# CellVoltageControl.net
KiCad netlist of a schematic drawn in Altium Designer
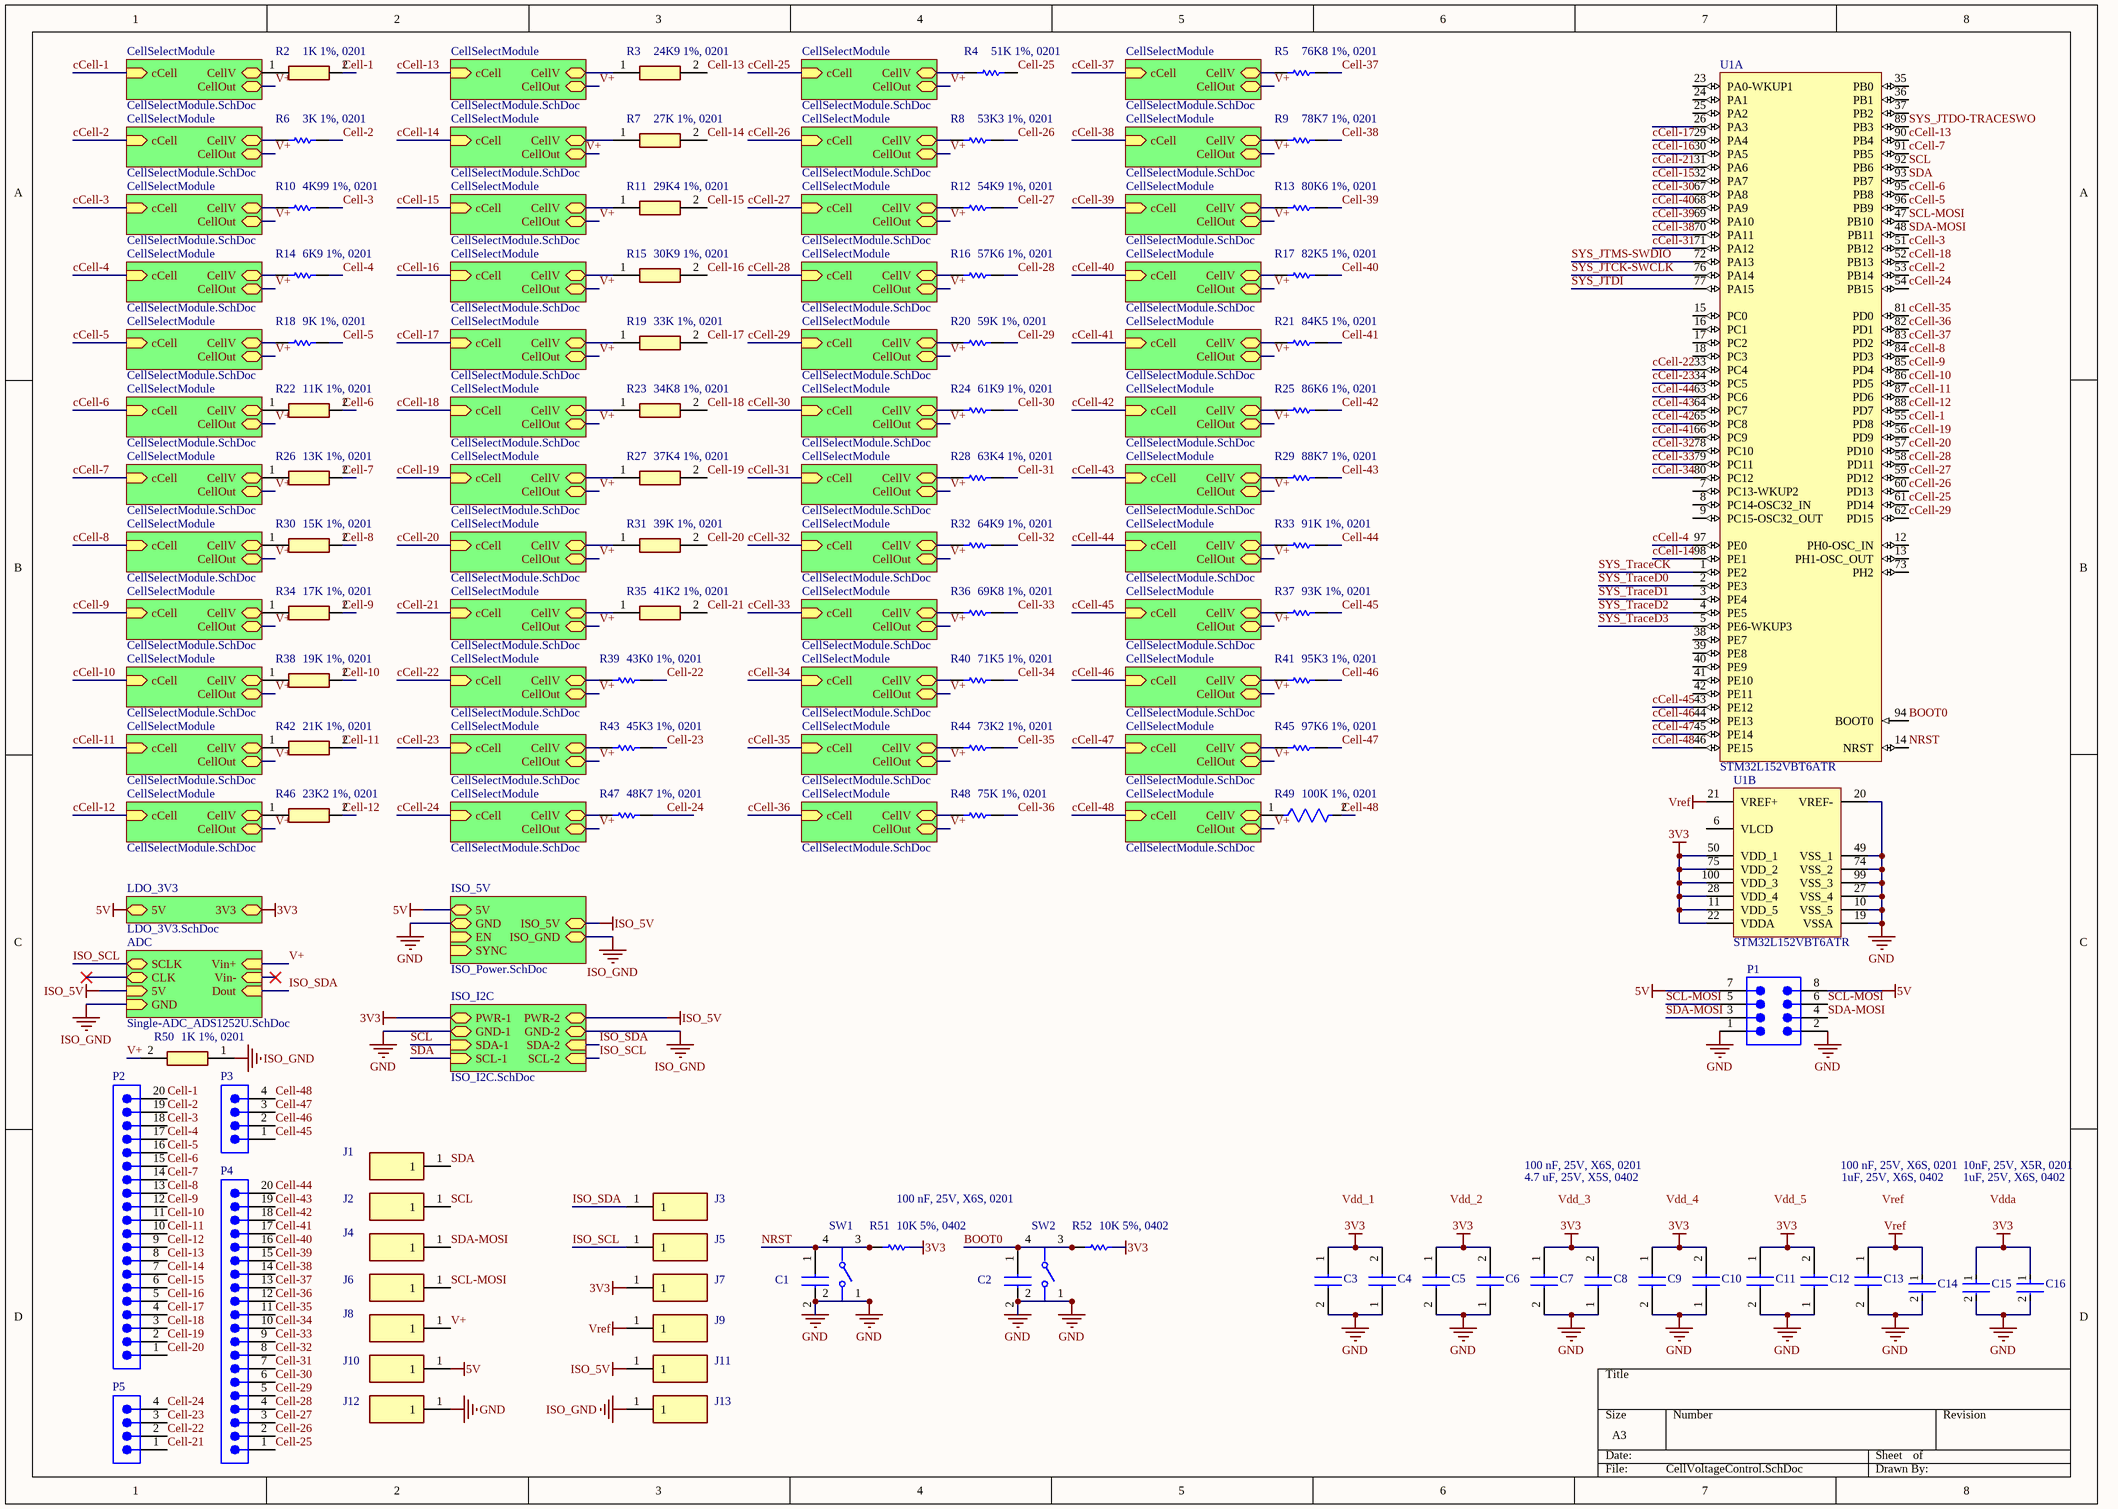
[diagram p0: CellVoltageControl.SchDoc]

(export (version "E")
  (design (tool "Eeschema 10.0.6"))
  (components
    (comp (ref "C1")
      (value "100 nF, 25V, X6S, 0201")
      (footprint "SamacSys:CAPC0603X33N")
      (description "Capacitor")
      (fields
        (field (name "MANUFACTURER_PART_NUMBER") "GRM033C81E104KE14D")
        (field (name "MOUSER PART NUMBER") "81-GRM33C81E104KE14D")
      )
      (libsource (lib "*") (part "GRM033C81E104KE14D"))
    )
    (comp (ref "C2")
      (value "100 nF, 25V, X6S, 0201")
      (footprint "SamacSys:CAPC0603X33N")
      (description "Capacitor")
      (fields
        (field (name "MANUFACTURER_PART_NUMBER") "GRM033C81E104KE14D")
        (field (name "MOUSER PART NUMBER") "81-GRM33C81E104KE14D")
      )
      (libsource (lib "*") (part "GRM033C81E104KE14D"))
    )
    (comp (ref "C3")
      (value "100 nF, 25V, X6S, 0201")
      (footprint "SamacSys:CAPC0603X33N")
      (description "Capacitor")
      (fields
        (field (name "MANUFACTURER_PART_NUMBER") "GRM033C81E104KE14D")
        (field (name "MOUSER PART NUMBER") "81-GRM33C81E104KE14D")
      )
      (libsource (lib "*") (part "GRM033C81E104KE14D"))
    )
    (comp (ref "C4")
      (value "4.7 uF, 25V, X5S, 0402")
      (footprint "SamacSys:GRM15x")
      (description "Capacitor")
      (fields
        (field (name "MANUFACTURER_PART_NUMBER") "GRM155C61E475ME15J")
        (field (name "MOUSER PART NUMBER") "81-GRM15C61E475ME15J")
      )
      (libsource (lib "*") (part "GRM155C61E475ME15J"))
    )
    (comp (ref "C5")
      (value "100 nF, 25V, X6S, 0201")
      (footprint "SamacSys:CAPC0603X33N")
      (description "Capacitor")
      (fields
        (field (name "MANUFACTURER_PART_NUMBER") "GRM033C81E104KE14D")
        (field (name "MOUSER PART NUMBER") "81-GRM33C81E104KE14D")
      )
      (libsource (lib "*") (part "GRM033C81E104KE14D"))
    )
    (comp (ref "C6")
      (value "4.7 uF, 25V, X5S, 0402")
      (footprint "SamacSys:GRM15x")
      (description "Capacitor")
      (fields
        (field (name "MANUFACTURER_PART_NUMBER") "GRM155C61E475ME15J")
        (field (name "MOUSER PART NUMBER") "81-GRM15C61E475ME15J")
      )
      (libsource (lib "*") (part "GRM155C61E475ME15J"))
    )
    (comp (ref "C7")
      (value "100 nF, 25V, X6S, 0201")
      (footprint "SamacSys:CAPC0603X33N")
      (description "Capacitor")
      (fields
        (field (name "MANUFACTURER_PART_NUMBER") "GRM033C81E104KE14D")
        (field (name "MOUSER PART NUMBER") "81-GRM33C81E104KE14D")
      )
      (libsource (lib "*") (part "GRM033C81E104KE14D"))
    )
    (comp (ref "C8")
      (value "4.7 uF, 25V, X5S, 0402")
      (footprint "SamacSys:GRM15x")
      (description "Capacitor")
      (fields
        (field (name "MANUFACTURER_PART_NUMBER") "GRM155C61E475ME15J")
        (field (name "MOUSER PART NUMBER") "81-GRM15C61E475ME15J")
      )
      (libsource (lib "*") (part "GRM155C61E475ME15J"))
    )
    (comp (ref "C9")
      (value "100 nF, 25V, X6S, 0201")
      (footprint "SamacSys:CAPC0603X33N")
      (description "Capacitor")
      (fields
        (field (name "MANUFACTURER_PART_NUMBER") "GRM033C81E104KE14D")
        (field (name "MOUSER PART NUMBER") "81-GRM33C81E104KE14D")
      )
      (libsource (lib "*") (part "GRM033C81E104KE14D"))
    )
    (comp (ref "C10")
      (value "4.7 uF, 25V, X5S, 0402")
      (footprint "SamacSys:GRM15x")
      (description "Capacitor")
      (fields
        (field (name "MANUFACTURER_PART_NUMBER") "GRM155C61E475ME15J")
        (field (name "MOUSER PART NUMBER") "81-GRM15C61E475ME15J")
      )
      (libsource (lib "*") (part "GRM155C61E475ME15J"))
    )
    (comp (ref "C11")
      (value "100 nF, 25V, X6S, 0201")
      (footprint "SamacSys:CAPC0603X33N")
      (description "Capacitor")
      (fields
        (field (name "MANUFACTURER_PART_NUMBER") "GRM033C81E104KE14D")
        (field (name "MOUSER PART NUMBER") "81-GRM33C81E104KE14D")
      )
      (libsource (lib "*") (part "GRM033C81E104KE14D"))
    )
    (comp (ref "C12")
      (value "4.7 uF, 25V, X5S, 0402")
      (footprint "SamacSys:GRM15x")
      (description "Capacitor")
      (fields
        (field (name "MANUFACTURER_PART_NUMBER") "GRM155C61E475ME15J")
        (field (name "MOUSER PART NUMBER") "81-GRM15C61E475ME15J")
      )
      (libsource (lib "*") (part "GRM155C61E475ME15J"))
    )
    (comp (ref "C13")
      (value "100 nF, 25V, X6S, 0201")
      (footprint "SamacSys:CAPC0603X33N")
      (description "Capacitor")
      (fields
        (field (name "MANUFACTURER_PART_NUMBER") "GRM033C81E104KE14D")
        (field (name "MOUSER PART NUMBER") "81-GRM33C81E104KE14D")
      )
      (libsource (lib "*") (part "GRM033C81E104KE14D"))
    )
    (comp (ref "C14")
      (value "1uF, 25V, X6S, 0402")
      (footprint "FP-GRT155-0_1-IPC_A")
      (description "Multi-Layer Ceramic Capacitor 1uF 25V X6S ±10% 0402 Paper T/R")
      (libsource (lib "Altium Content Vault") (part "02cd4be3c70576c341d710602a673aa"))
    )
    (comp (ref "C15")
      (value "10nF, 25V, X5R, 0201")
      (footprint "FP-GRM033-0_03-IPC_C")
      (description "Chip Multilayer Ceramic Capacitors for General Purpose, 0201, 10000pF, X5R, 15%, 10%, 25V")
      (fields (field (name "TOLERANCE") "10%") (field (name "VOLTAGE") "25V"))
      (libsource (lib "Altium Content Vault") (part "b4654b650e69147ec39a6b967a45e02"))
    )
    (comp (ref "C16")
      (value "1uF, 25V, X6S, 0402")
      (footprint "FP-GRT155-0_1-IPC_A")
      (description "Multi-Layer Ceramic Capacitor 1uF 25V X6S ±10% 0402 Paper T/R")
      (libsource (lib "Altium Content Vault") (part "02cd4be3c70576c341d710602a673aa"))
    )
    (comp (ref "J1")
      (value "TestPad")
      (footprint "SamacSys:TestPad")
      (description "Connector")
      (fields
        (field (name "MANUFACTURER_PART_NUMBER") "61300111121")
        (field (name "MOUSER PART NUMBER") "710-61300111121")
      )
      (libsource (lib "*") (part "61300111121"))
    )
    (comp (ref "J2")
      (value "TestPad")
      (footprint "SamacSys:TestPad")
      (description "Connector")
      (fields
        (field (name "MANUFACTURER_PART_NUMBER") "61300111121")
        (field (name "MOUSER PART NUMBER") "710-61300111121")
      )
      (libsource (lib "*") (part "61300111121"))
    )
    (comp (ref "J3")
      (value "TestPad")
      (footprint "SamacSys:TestPad")
      (description "Connector")
      (fields
        (field (name "MANUFACTURER_PART_NUMBER") "61300111121")
        (field (name "MOUSER PART NUMBER") "710-61300111121")
      )
      (libsource (lib "") (part "61300111121_1"))
    )
    (comp (ref "J4")
      (value "TestPad")
      (footprint "SamacSys:TestPad")
      (description "Connector")
      (fields
        (field (name "MANUFACTURER_PART_NUMBER") "61300111121")
        (field (name "MOUSER PART NUMBER") "710-61300111121")
      )
      (libsource (lib "*") (part "61300111121"))
    )
    (comp (ref "J5")
      (value "TestPad")
      (footprint "SamacSys:TestPad")
      (description "Connector")
      (fields
        (field (name "MANUFACTURER_PART_NUMBER") "61300111121")
        (field (name "MOUSER PART NUMBER") "710-61300111121")
      )
      (libsource (lib "") (part "61300111121_1"))
    )
    (comp (ref "J6")
      (value "TestPad")
      (footprint "SamacSys:TestPad")
      (description "Connector")
      (fields
        (field (name "MANUFACTURER_PART_NUMBER") "61300111121")
        (field (name "MOUSER PART NUMBER") "710-61300111121")
      )
      (libsource (lib "*") (part "61300111121"))
    )
    (comp (ref "J7")
      (value "TestPad")
      (footprint "SamacSys:TestPad")
      (description "Connector")
      (fields
        (field (name "MANUFACTURER_PART_NUMBER") "61300111121")
        (field (name "MOUSER PART NUMBER") "710-61300111121")
      )
      (libsource (lib "") (part "61300111121_1"))
    )
    (comp (ref "J8")
      (value "TestPad")
      (footprint "SamacSys:TestPad")
      (description "Connector")
      (fields
        (field (name "MANUFACTURER_PART_NUMBER") "61300111121")
        (field (name "MOUSER PART NUMBER") "710-61300111121")
      )
      (libsource (lib "*") (part "61300111121"))
    )
    (comp (ref "J9")
      (value "TestPad")
      (footprint "SamacSys:TestPad")
      (description "Connector")
      (fields
        (field (name "MANUFACTURER_PART_NUMBER") "61300111121")
        (field (name "MOUSER PART NUMBER") "710-61300111121")
      )
      (libsource (lib "") (part "61300111121_1"))
    )
    (comp (ref "J10")
      (value "TestPad")
      (footprint "SamacSys:TestPad")
      (description "Connector")
      (fields
        (field (name "MANUFACTURER_PART_NUMBER") "61300111121")
        (field (name "MOUSER PART NUMBER") "710-61300111121")
      )
      (libsource (lib "*") (part "61300111121"))
    )
    (comp (ref "J11")
      (value "TestPad")
      (footprint "SamacSys:TestPad")
      (description "Connector")
      (fields
        (field (name "MANUFACTURER_PART_NUMBER") "61300111121")
        (field (name "MOUSER PART NUMBER") "710-61300111121")
      )
      (libsource (lib "") (part "61300111121_1"))
    )
    (comp (ref "J12")
      (value "TestPad")
      (footprint "SamacSys:TestPad")
      (description "Connector")
      (fields
        (field (name "MANUFACTURER_PART_NUMBER") "61300111121")
        (field (name "MOUSER PART NUMBER") "710-61300111121")
      )
      (libsource (lib "*") (part "61300111121"))
    )
    (comp (ref "J13")
      (value "TestPad")
      (footprint "SamacSys:TestPad")
      (description "Connector")
      (fields
        (field (name "MANUFACTURER_PART_NUMBER") "61300111121")
        (field (name "MOUSER PART NUMBER") "710-61300111121")
      )
      (libsource (lib "") (part "61300111121_1"))
    )
    (comp (ref "P1")
      (value "61200821621")
      (footprint "61200821621")
      (libsource (lib "Altium Content Vault") (part "Header_Male_2R_08P"))
    )
    (comp (ref "P2")
      (value "61302011121")
      (footprint "61302011121")
      (libsource (lib "Altium Content Vault") (part "Header_Male_1R_20P"))
    )
    (comp (ref "P3")
      (value "61300411121")
      (footprint "61300411121")
      (libsource (lib "Altium Content Vault") (part "Header_Male_1R_04P"))
    )
    (comp (ref "P4")
      (value "61302011121")
      (footprint "61302011121")
      (libsource (lib "Altium Content Vault") (part "Header_Male_1R_20P"))
    )
    (comp (ref "P5")
      (value "61300411121")
      (footprint "61300411121")
      (libsource (lib "Altium Content Vault") (part "Header_Male_1R_04P"))
    )
    (comp (ref "R2")
      (value "1K 1%, 0201")
      (footprint "SamacSys:ERJ1GN_(0201)")
      (description "Resistor")
      (fields
        (field (name "MANUFACTURER_PART_NUMBER") "ERJ-1GNF1001C")
        (field (name "MOUSER PART NUMBER") "667-ERJ-1GNF1001C")
      )
      (libsource (lib "*") (part "ERJ-1GNF1001C"))
    )
    (comp (ref "R3")
      (value "24K9 1%, 0201")
      (footprint "SamacSys:ERJ1GN_(0201)")
      (description "Resistor")
      (fields
        (field (name "MANUFACTURER_PART_NUMBER") "ERJ-1GNF2492C")
        (field (name "MOUSER PART NUMBER") "667-ERJ-1GNF2492C")
      )
      (libsource (lib "*") (part "ERJ-1GNF2492C"))
    )
    (comp (ref "R4")
      (value "51K 1%, 0201")
      (footprint "RESC0603X26X15NL03T05")
      (fields (field (name "PART NUMBER") "ERJ1GNF5102C") (field (name "MANUFACTURER") "Panasonic"))
      (libsource (lib "Altium Content Vault") (part "RES"))
    )
    (comp (ref "R5")
      (value "76K8 1%, 0201")
      (footprint "RESC0603X26X15LL03T05")
      (fields (field (name "MANUFACTURER") "Panasonic") (field (name "PART NUMBER") "ERJ-1GNF7682C"))
      (libsource (lib "Altium Content Vault") (part "RES"))
    )
    (comp (ref "R6")
      (value "3K 1%, 0201")
      (footprint "RESC0603X26X15ML03T05")
      (fields (field (name "MANUFACTURER") "Panasonic") (field (name "PART NUMBER") "ERJ1GNF3001C"))
      (libsource (lib "Altium Content Vault") (part "RES"))
    )
    (comp (ref "R7")
      (value "27K 1%, 0201")
      (footprint "SamacSys:ERJ1GN_(0201)")
      (description "Resistor")
      (fields
        (field (name "MANUFACTURER_PART_NUMBER") "ERJ-1GNF2702C")
        (field (name "MOUSER PART NUMBER") "667-ERJ-1GNF2702C")
      )
      (libsource (lib "*") (part "ERJ-1GNF2702C"))
    )
    (comp (ref "R8")
      (value "53K3 1%, 0201")
      (footprint "RESC0201(0603)_M")
      (description "53K6 0.05W 1% 0201 (0603 Metric)  SMD")
      (fields (field (name "POWER") "0.05 W") (field (name "TOLERANCE") "1 %"))
      (libsource (lib "Altium Content Vault") (part "RES"))
    )
    (comp (ref "R9")
      (value "78K7 1%, 0201")
      (footprint "RESC0603X26X15NL03T05")
      (fields (field (name "PART NUMBER") "ERJ-1GNF7872C") (field (name "MANUFACTURER") "Panasonic"))
      (libsource (lib "Altium Content Vault") (part "RES"))
    )
    (comp (ref "R10")
      (value "4K99 1%, 0201")
      (footprint "RESC0603X26X15LL03T05")
      (fields (field (name "PART NUMBER") "ERJ-1GNF4991C") (field (name "MANUFACTURER") "Panasonic"))
      (libsource (lib "Altium Content Vault") (part "RES"))
    )
    (comp (ref "R11")
      (value "29K4 1%, 0201")
      (footprint "SamacSys:ERJ1GN_(0201)")
      (description "Resistor")
      (fields
        (field (name "MANUFACTURER_PART_NUMBER") "ERJ-1GNF2942C")
        (field (name "MOUSER PART NUMBER") "667-ERJ-1GNF2942C")
      )
      (libsource (lib "*") (part "ERJ-1GNF2942C"))
    )
    (comp (ref "R12")
      (value "54K9 1%, 0201")
      (footprint "RESC0603X26X15NL03T05")
      (fields (field (name "MANUFACTURER") "Panasonic") (field (name "PART NUMBER") "ERJ-1GNF5492C"))
      (libsource (lib "Altium Content Vault") (part "RES"))
    )
    (comp (ref "R13")
      (value "80K6 1%, 0201")
      (footprint "RESC0201(0603)_L")
      (description "80K6 0.05W 1% 0201 (0603 Metric)  SMD")
      (fields (field (name "POWER") "0.05 W") (field (name "TOLERANCE") "1 %"))
      (libsource (lib "Altium Content Vault") (part "RES"))
    )
    (comp (ref "R14")
      (value "6K9 1%, 0201")
      (footprint "RESC0603X26X15NL03T05")
      (fields (field (name "MANUFACTURER") "Panasonic") (field (name "PART NUMBER") "ERJ-1GNF6981C"))
      (libsource (lib "Altium Content Vault") (part "RES"))
    )
    (comp (ref "R15")
      (value "30K9 1%, 0201")
      (footprint "SamacSys:ERJ1GN_(0201)")
      (description "Resistor")
      (fields
        (field (name "MANUFACTURER_PART_NUMBER") "ERJ-1GNF3092C")
        (field (name "MOUSER PART NUMBER") "667-ERJ-1GNF3092C")
      )
      (libsource (lib "*") (part "ERJ-1GNF3092C"))
    )
    (comp (ref "R16")
      (value "57K6 1%, 0201")
      (footprint "RESC0603X26X15NL03T05")
      (fields (field (name "PART NUMBER") "ERJ-1GEF5762C") (field (name "MANUFACTURER") "Panasonic"))
      (libsource (lib "Altium Content Vault") (part "RES"))
    )
    (comp (ref "R17")
      (value "82K5 1%, 0201")
      (footprint "RESC0603X26X15NL03T05")
      (fields (field (name "PART NUMBER") "ERJ-1GNF8252C") (field (name "MANUFACTURER") "Panasonic"))
      (libsource (lib "Altium Content Vault") (part "RES"))
    )
    (comp (ref "R18")
      (value "9K 1%, 0201")
      (footprint "RESC0603X26X15NL03T05")
      (fields (field (name "PART NUMBER") "ERJ-1GNF9091C") (field (name "MANUFACTURER") "Panasonic"))
      (libsource (lib "Altium Content Vault") (part "RES"))
    )
    (comp (ref "R19")
      (value "33K 1%, 0201")
      (footprint "SamacSys:ERJ1GN_(0201)")
      (description "Resistor")
      (fields
        (field (name "MANUFACTURER_PART_NUMBER") "ERJ-1GNF3302C")
        (field (name "MOUSER PART NUMBER") "667-ERJ-1GNF3302C")
      )
      (libsource (lib "*") (part "ERJ-1GNF3302C"))
    )
    (comp (ref "R20")
      (value "59K 1%, 0201")
      (footprint "RESC0603X26X15NL03T05")
      (fields (field (name "MANUFACTURER") "Panasonic") (field (name "PART NUMBER") "ERJ-1GEF5902C"))
      (libsource (lib "Altium Content Vault") (part "RES"))
    )
    (comp (ref "R21")
      (value "84K5 1%, 0201")
      (footprint "RESC0603X26X15NL03T05")
      (fields (field (name "MANUFACTURER") "Panasonic") (field (name "PART NUMBER") "ERJ-1GNF8452C"))
      (libsource (lib "Altium Content Vault") (part "RES"))
    )
    (comp (ref "R22")
      (value "11K 1%, 0201")
      (footprint "SamacSys:ERJ1GN_(0201)")
      (description "Resistor")
      (fields (field (name "MANUFACTURER_PART_NUMBER") "ERJ-1GNF1102C"))
      (libsource (lib "*") (part "ERJ-1GNF1102C"))
    )
    (comp (ref "R23")
      (value "34K8 1%, 0201")
      (footprint "SamacSys:ERJ1GN_(0201)")
      (description "Resistor")
      (fields
        (field (name "MANUFACTURER_PART_NUMBER") "ERJ-1GNF3482C")
        (field (name "MOUSER PART NUMBER") "667-ERJ-1GNF3482C")
      )
      (libsource (lib "*") (part "ERJ-1GNF3482C"))
    )
    (comp (ref "R24")
      (value "61K9 1%, 0201")
      (footprint "RESC0603X26X15NL03T05")
      (fields (field (name "PART NUMBER") "ERJ-1GNF6192C") (field (name "MANUFACTURER") "Panasonic"))
      (libsource (lib "Altium Content Vault") (part "RES"))
    )
    (comp (ref "R25")
      (value "86K6 1%, 0201")
      (footprint "RESC0603X26X15LL03T05")
      (fields (field (name "MANUFACTURER") "Panasonic") (field (name "PART NUMBER") "ERJ-1GNF8662C"))
      (libsource (lib "Altium Content Vault") (part "RES"))
    )
    (comp (ref "R26")
      (value "13K 1%, 0201")
      (footprint "SamacSys:ERJ1GN_(0201)")
      (description "Resistor")
      (fields (field (name "MANUFACTURER_PART_NUMBER") "ERJ-1GNF1302C"))
      (libsource (lib "*") (part "ERJ-1GNF1302C"))
    )
    (comp (ref "R27")
      (value "37K4 1%, 0201")
      (footprint "SamacSys:ERJ1GN_(0201)")
      (description "Resistor")
      (fields
        (field (name "MANUFACTURER_PART_NUMBER") "ERJ-1GNF3742C")
        (field (name "MOUSER PART NUMBER") "667-ERJ-1GNF3742C")
      )
      (libsource (lib "*") (part "ERJ-1GNF3742C"))
    )
    (comp (ref "R28")
      (value "63K4 1%, 0201")
      (footprint "RESC0201(0603)_M")
      (description "63K4 0.05W 1% 0201 (0603 Metric)  SMD")
      (fields (field (name "TOLERANCE") "1 %") (field (name "POWER") "0.05 W"))
      (libsource (lib "Altium Content Vault") (part "RES"))
    )
    (comp (ref "R29")
      (value "88K7 1%, 0201")
      (footprint "RESC0603X26X15LL03T05")
      (fields (field (name "MANUFACTURER") "Panasonic") (field (name "PART NUMBER") "ERJ-1GNF8872C"))
      (libsource (lib "Altium Content Vault") (part "RES"))
    )
    (comp (ref "R30")
      (value "15K 1%, 0201")
      (footprint "SamacSys:ERJ1GJJ2R4C")
      (description "Resistor")
      (fields
        (field (name "MANUFACTURER_PART_NUMBER") "ERJ-1GJF1502C")
        (field (name "MOUSER PART NUMBER") "667-ERJ-1GJF1502C")
      )
      (libsource (lib "*") (part "ERJ-1GJF1502C"))
    )
    (comp (ref "R31")
      (value "39K 1%, 0201")
      (footprint "SamacSys:ERJ1GN_(0201)")
      (description "Resistor")
      (fields
        (field (name "MANUFACTURER_PART_NUMBER") "ERJ-1GNF3902C")
        (field (name "MOUSER PART NUMBER") "667-ERJ-1GNF3902C")
      )
      (libsource (lib "*") (part "ERJ-1GNF3902C"))
    )
    (comp (ref "R32")
      (value "64K9 1%, 0201")
      (footprint "RESC0603X26X15LL03T05")
      (fields (field (name "PART NUMBER") "ERJ-1GNF6492C") (field (name "MANUFACTURER") "Panasonic"))
      (libsource (lib "Altium Content Vault") (part "RES"))
    )
    (comp (ref "R33")
      (value "91K 1%, 0201")
      (footprint "RESC0603X26X15NL03T05")
      (fields (field (name "PART NUMBER") "ERJ1GNF9102C") (field (name "MANUFACTURER") "Panasonic"))
      (libsource (lib "Altium Content Vault") (part "RES"))
    )
    (comp (ref "R34")
      (value "17K 1%, 0201")
      (footprint "SamacSys:ERJ1GN_(0201)")
      (description "Resistor")
      (fields
        (field (name "MANUFACTURER_PART_NUMBER") "ERJ-1GNF1692C")
        (field (name "MOUSER PART NUMBER") "667-ERJ-1GNF1692C")
      )
      (libsource (lib "*") (part "ERJ-1GNF1692C"))
    )
    (comp (ref "R35")
      (value "41K2 1%, 0201")
      (footprint "SamacSys:ERJ1GN_(0201)")
      (description "Resistor")
      (fields (field (name "MANUFACTURER_PART_NUMBER") "ERJ-1GNF4122C"))
      (libsource (lib "*") (part "ERJ-1GNF4122C"))
    )
    (comp (ref "R36")
      (value "69K8 1%, 0201")
      (footprint "RESC0603X26X15LL03T05")
      (fields (field (name "MANUFACTURER") "Panasonic") (field (name "PART NUMBER") "ERJ-1GEF6982C"))
      (libsource (lib "Altium Content Vault") (part "RES"))
    )
    (comp (ref "R37")
      (value "93K 1%, 0201")
      (footprint "RESC0201(0603)_L")
      (description "93K1 0.05W 1% 0201 (0603 Metric)  SMD")
      (fields (field (name "TOLERANCE") "1 %") (field (name "POWER") "0.05 W"))
      (libsource (lib "Altium Content Vault") (part "RES"))
    )
    (comp (ref "R38")
      (value "19K 1%, 0201")
      (footprint "SamacSys:ERJ1GN_(0201)")
      (description "Resistor")
      (fields
        (field (name "MANUFACTURER_PART_NUMBER") "ERJ-1GNF1912C")
        (field (name "MOUSER PART NUMBER") "667-ERJ-1GNF1912C")
      )
      (libsource (lib "*") (part "ERJ-1GNF1912C"))
    )
    (comp (ref "R39")
      (value "43K0 1%, 0201")
      (footprint "RESC0603X26X15LL03T05")
      (fields (field (name "MANUFACTURER") "Panasonic") (field (name "PART NUMBER") "ERJ1GNF4302C"))
      (libsource (lib "Altium Content Vault") (part "RES"))
    )
    (comp (ref "R40")
      (value "71K5 1%, 0201")
      (footprint "RESC0603X26X15LL03T05")
      (fields (field (name "MANUFACTURER") "Panasonic") (field (name "PART NUMBER") "ERJ-1GNF7152C"))
      (libsource (lib "Altium Content Vault") (part "RES"))
    )
    (comp (ref "R41")
      (value "95K3 1%, 0201")
      (footprint "RESC0603X26X15ML03T05")
      (fields (field (name "MANUFACTURER") "Panasonic") (field (name "PART NUMBER") "ERJ-1GNF9532C"))
      (libsource (lib "Altium Content Vault") (part "RES"))
    )
    (comp (ref "R42")
      (value "21K 1%, 0201")
      (footprint "SamacSys:ERJ1GN_(0201)")
      (description "Resistor")
      (fields
        (field (name "MANUFACTURER_PART_NUMBER") "ERJ-1GNF2102C")
        (field (name "MOUSER PART NUMBER") "667-ERJ-1GNF2102C")
      )
      (libsource (lib "*") (part "ERJ-1GNF2102C"))
    )
    (comp (ref "R43")
      (value "45K3 1%, 0201")
      (footprint "RESC0201(0603)_N")
      (description "45K3 0.05W 1% 0201 (0603 Metric)  SMD")
      (fields (field (name "TOLERANCE") "1 %") (field (name "POWER") "0.05 W"))
      (libsource (lib "Altium Content Vault") (part "RES"))
    )
    (comp (ref "R44")
      (value "73K2 1%, 0201")
      (footprint "RESC0603X26X15NL03T05")
      (fields (field (name "MANUFACTURER") "Panasonic") (field (name "PART NUMBER") "ERJ-1GNF7322C"))
      (libsource (lib "Altium Content Vault") (part "RES"))
    )
    (comp (ref "R45")
      (value "97K6 1%, 0201")
      (footprint "RESC0603X26X15ML03T05")
      (fields (field (name "MANUFACTURER") "Panasonic") (field (name "PART NUMBER") "ERJ-1GNF9762C"))
      (libsource (lib "Altium Content Vault") (part "RES"))
    )
    (comp (ref "R46")
      (value "23K2 1%, 0201")
      (footprint "SamacSys:ERJ1GN_(0201)")
      (description "Resistor")
      (fields (field (name "MANUFACTURER_PART_NUMBER") "ERJ-1GNF2322C"))
      (libsource (lib "*") (part "ERJ-1GNF2322C"))
    )
    (comp (ref "R47")
      (value "48K7 1%, 0201")
      (footprint "RESC0603X26X15LL03T05")
      (fields (field (name "MANUFACTURER") "Panasonic") (field (name "PART NUMBER") "ERJ-1GEF4872C"))
      (libsource (lib "Altium Content Vault") (part "RES"))
    )
    (comp (ref "R48")
      (value "75K 1%, 0201")
      (footprint "RESC0603X26X15ML03T05")
      (fields (field (name "MANUFACTURER") "Panasonic") (field (name "PART NUMBER") "ERJ1GNF7502C"))
      (libsource (lib "Altium Content Vault") (part "RES"))
    )
    (comp (ref "R49")
      (value "100K 1%, 0201")
      (footprint "FP-ERJ1GN-IPC_A")
      (description "RES SMD 100K OHM 1% 1/20W 0201")
      (fields (field (name "TOLERANCE") "1%"))
      (libsource (lib "Altium Content Vault") (part "1029c3af85768c4190bb7ad29bc67b5"))
    )
    (comp (ref "R50")
      (value "1K 1%, 0201")
      (footprint "SamacSys:ERJ1GN_(0201)")
      (description "Resistor")
      (fields
        (field (name "MANUFACTURER_PART_NUMBER") "ERJ-1GNF1001C")
        (field (name "MOUSER PART NUMBER") "667-ERJ-1GNF1001C")
      )
      (libsource (lib "") (part "ERJ-1GNF1001C_1"))
    )
    (comp (ref "R51")
      (value "10K 5%, 0402")
      (footprint "RESC1005X40X25ML05T05")
      (fields (field (name "PART NUMBER") "ERJ-2GEJ103X") (field (name "MANUFACTURER") "Panasonic"))
      (libsource (lib "Altium Content Vault") (part "RES"))
    )
    (comp (ref "R52")
      (value "10K 5%, 0402")
      (footprint "RESC1005X40X25ML05T05")
      (fields (field (name "PART NUMBER") "ERJ-2GEJ103X") (field (name "MANUFACTURER") "Panasonic"))
      (libsource (lib "Altium Content Vault") (part "RES"))
    )
    (comp (ref "SW1")
      (value "PTS810SJM250SMTRLFS")
      (footprint "FP-PTS810SJM250SMTRLFS-MFG")
      (description "SWITCH TACTILE SPST-NO 0.05A 16V")
      (libsource (lib "Altium Content Vault") (part "1adf0dd01260c80cf25a44bfd6b99ba"))
    )
    (comp (ref "SW2")
      (value "PTS810SJM250SMTRLFS")
      (footprint "FP-PTS810SJM250SMTRLFS-MFG")
      (description "SWITCH TACTILE SPST-NO 0.05A 16V")
      (libsource (lib "Altium Content Vault") (part "1adf0dd01260c80cf25a44bfd6b99ba"))
    )
    (comp (ref "U1")
      (value "STM32L152VBT6ATR")
      (footprint "STM-LQFP100_L")
      (fields (field (name "MANUFACTURER") "STMicroelectronics"))
      (libsource (lib "Altium Content Vault") (part "MC-ARM-STM32L15X-LQFP100"))
    )
  )
  (nets
    (net (code "1") (name "/BOOT0") (class "Default")
      (node (ref "C2") (pin "1") (pinfunction "1_1") (pintype "passive"))
      (node (ref "R52") (pin "2") (pinfunction "2_2") (pintype "passive"))
      (node (ref "SW2") (pin "3") (pinfunction "3_3") (pintype "passive"))
      (node (ref "SW2") (pin "4") (pinfunction "4_4") (pintype "passive"))
      (node (ref "U1") (pin "94") (pinfunction "BOOT0_94") (pintype "input"))
    )
    (net (code "3") (name "/Cell-1") (class "Default")
      (node (ref "P2") (pin "20") (pinfunction "20_20") (pintype "passive"))
      (node (ref "R2") (pin "2") (pinfunction "2_2") (pintype "passive"))
    )
    (net (code "4") (name "/Cell-2") (class "Default")
      (node (ref "P2") (pin "19") (pinfunction "19_19") (pintype "passive"))
      (node (ref "R6") (pin "2") (pinfunction "2_2") (pintype "passive"))
    )
    (net (code "5") (name "/Cell-3") (class "Default")
      (node (ref "P2") (pin "18") (pinfunction "18_18") (pintype "passive"))
      (node (ref "R10") (pin "2") (pinfunction "2_2") (pintype "passive"))
    )
    (net (code "6") (name "/Cell-4") (class "Default")
      (node (ref "P2") (pin "17") (pinfunction "17_17") (pintype "passive"))
      (node (ref "R14") (pin "2") (pinfunction "2_2") (pintype "passive"))
    )
    (net (code "7") (name "/Cell-5") (class "Default")
      (node (ref "P2") (pin "16") (pinfunction "16_16") (pintype "passive"))
      (node (ref "R18") (pin "2") (pinfunction "2_2") (pintype "passive"))
    )
    (net (code "8") (name "/Cell-6") (class "Default")
      (node (ref "P2") (pin "15") (pinfunction "15_15") (pintype "passive"))
      (node (ref "R22") (pin "2") (pinfunction "2_2") (pintype "passive"))
    )
    (net (code "9") (name "/Cell-7") (class "Default")
      (node (ref "P2") (pin "14") (pinfunction "14_14") (pintype "passive"))
      (node (ref "R26") (pin "2") (pinfunction "2_2") (pintype "passive"))
    )
    (net (code "10") (name "/Cell-8") (class "Default")
      (node (ref "P2") (pin "13") (pinfunction "13_13") (pintype "passive"))
      (node (ref "R30") (pin "2") (pinfunction "2_2") (pintype "passive"))
    )
    (net (code "11") (name "/Cell-9") (class "Default")
      (node (ref "P2") (pin "12") (pinfunction "12_12") (pintype "passive"))
      (node (ref "R34") (pin "2") (pinfunction "2_2") (pintype "passive"))
    )
    (net (code "12") (name "/Cell-10") (class "Default")
      (node (ref "P2") (pin "11") (pinfunction "11_11") (pintype "passive"))
      (node (ref "R38") (pin "2") (pinfunction "2_2") (pintype "passive"))
    )
    (net (code "13") (name "/Cell-11") (class "Default")
      (node (ref "P2") (pin "10") (pinfunction "10_10") (pintype "passive"))
      (node (ref "R42") (pin "2") (pinfunction "2_2") (pintype "passive"))
    )
    (net (code "14") (name "/Cell-12") (class "Default")
      (node (ref "P2") (pin "9") (pinfunction "9_9") (pintype "passive"))
      (node (ref "R46") (pin "2") (pinfunction "2_2") (pintype "passive"))
    )
    (net (code "15") (name "/Cell-13") (class "Default")
      (node (ref "P2") (pin "8") (pinfunction "8_8") (pintype "passive"))
      (node (ref "R3") (pin "2") (pinfunction "2_2") (pintype "passive"))
    )
    (net (code "16") (name "/Cell-14") (class "Default")
      (node (ref "P2") (pin "7") (pinfunction "7_7") (pintype "passive"))
      (node (ref "R7") (pin "2") (pinfunction "2_2") (pintype "passive"))
    )
    (net (code "17") (name "/Cell-15") (class "Default")
      (node (ref "P2") (pin "6") (pinfunction "6_6") (pintype "passive"))
      (node (ref "R11") (pin "2") (pinfunction "2_2") (pintype "passive"))
    )
    (net (code "18") (name "/Cell-16") (class "Default")
      (node (ref "P2") (pin "5") (pinfunction "5_5") (pintype "passive"))
      (node (ref "R15") (pin "2") (pinfunction "2_2") (pintype "passive"))
    )
    (net (code "19") (name "/Cell-17") (class "Default")
      (node (ref "P2") (pin "4") (pinfunction "4_4") (pintype "passive"))
      (node (ref "R19") (pin "2") (pinfunction "2_2") (pintype "passive"))
    )
    (net (code "20") (name "/Cell-18") (class "Default")
      (node (ref "P2") (pin "3") (pinfunction "3_3") (pintype "passive"))
      (node (ref "R23") (pin "2") (pinfunction "2_2") (pintype "passive"))
    )
    (net (code "21") (name "/Cell-19") (class "Default")
      (node (ref "P2") (pin "2") (pinfunction "2_2") (pintype "passive"))
      (node (ref "R27") (pin "2") (pinfunction "2_2") (pintype "passive"))
    )
    (net (code "22") (name "/Cell-20") (class "Default")
      (node (ref "P2") (pin "1") (pinfunction "1_1") (pintype "passive"))
      (node (ref "R31") (pin "2") (pinfunction "2_2") (pintype "passive"))
    )
    (net (code "23") (name "/Cell-21") (class "Default")
      (node (ref "P5") (pin "1") (pinfunction "1_1") (pintype "passive"))
      (node (ref "R35") (pin "2") (pinfunction "2_2") (pintype "passive"))
    )
    (net (code "24") (name "/Cell-22") (class "Default")
      (node (ref "P5") (pin "2") (pinfunction "2_2") (pintype "passive"))
      (node (ref "R39") (pin "2") (pinfunction "2_2") (pintype "passive"))
    )
    (net (code "25") (name "/Cell-23") (class "Default")
      (node (ref "P5") (pin "3") (pinfunction "3_3") (pintype "passive"))
      (node (ref "R43") (pin "2") (pinfunction "2_2") (pintype "passive"))
    )
    (net (code "26") (name "/Cell-24") (class "Default")
      (node (ref "P5") (pin "4") (pinfunction "4_4") (pintype "passive"))
      (node (ref "R47") (pin "2") (pinfunction "2_2") (pintype "passive"))
    )
    (net (code "27") (name "/Cell-25") (class "Default")
      (node (ref "P4") (pin "1") (pinfunction "1_1") (pintype "passive"))
      (node (ref "R4") (pin "2") (pinfunction "2_2") (pintype "passive"))
    )
    (net (code "28") (name "/Cell-26") (class "Default")
      (node (ref "P4") (pin "2") (pinfunction "2_2") (pintype "passive"))
      (node (ref "R8") (pin "2") (pinfunction "2_2") (pintype "passive"))
    )
    (net (code "29") (name "/Cell-27") (class "Default")
      (node (ref "P4") (pin "3") (pinfunction "3_3") (pintype "passive"))
      (node (ref "R12") (pin "2") (pinfunction "2_2") (pintype "passive"))
    )
    (net (code "30") (name "/Cell-28") (class "Default")
      (node (ref "P4") (pin "4") (pinfunction "4_4") (pintype "passive"))
      (node (ref "R16") (pin "2") (pinfunction "2_2") (pintype "passive"))
    )
    (net (code "31") (name "/Cell-29") (class "Default")
      (node (ref "P4") (pin "5") (pinfunction "5_5") (pintype "passive"))
      (node (ref "R20") (pin "2") (pinfunction "2_2") (pintype "passive"))
    )
    (net (code "32") (name "/Cell-30") (class "Default")
      (node (ref "P4") (pin "6") (pinfunction "6_6") (pintype "passive"))
      (node (ref "R24") (pin "2") (pinfunction "2_2") (pintype "passive"))
    )
    (net (code "33") (name "/Cell-31") (class "Default")
      (node (ref "P4") (pin "7") (pinfunction "7_7") (pintype "passive"))
      (node (ref "R28") (pin "2") (pinfunction "2_2") (pintype "passive"))
    )
    (net (code "34") (name "/Cell-32") (class "Default")
      (node (ref "P4") (pin "8") (pinfunction "8_8") (pintype "passive"))
      (node (ref "R32") (pin "2") (pinfunction "2_2") (pintype "passive"))
    )
    (net (code "35") (name "/Cell-33") (class "Default")
      (node (ref "P4") (pin "9") (pinfunction "9_9") (pintype "passive"))
      (node (ref "R36") (pin "2") (pinfunction "2_2") (pintype "passive"))
    )
    (net (code "36") (name "/Cell-34") (class "Default")
      (node (ref "P4") (pin "10") (pinfunction "10_10") (pintype "passive"))
      (node (ref "R40") (pin "2") (pinfunction "2_2") (pintype "passive"))
    )
    (net (code "37") (name "/Cell-35") (class "Default")
      (node (ref "P4") (pin "11") (pinfunction "11_11") (pintype "passive"))
      (node (ref "R44") (pin "2") (pinfunction "2_2") (pintype "passive"))
    )
    (net (code "38") (name "/Cell-36") (class "Default")
      (node (ref "P4") (pin "12") (pinfunction "12_12") (pintype "passive"))
      (node (ref "R48") (pin "2") (pinfunction "2_2") (pintype "passive"))
    )
    (net (code "39") (name "/Cell-37") (class "Default")
      (node (ref "P4") (pin "13") (pinfunction "13_13") (pintype "passive"))
      (node (ref "R5") (pin "2") (pinfunction "2_2") (pintype "passive"))
    )
    (net (code "40") (name "/Cell-38") (class "Default")
      (node (ref "P4") (pin "14") (pinfunction "14_14") (pintype "passive"))
      (node (ref "R9") (pin "2") (pinfunction "2_2") (pintype "passive"))
    )
    (net (code "41") (name "/Cell-39") (class "Default")
      (node (ref "P4") (pin "15") (pinfunction "15_15") (pintype "passive"))
      (node (ref "R13") (pin "2") (pinfunction "2_2") (pintype "passive"))
    )
    (net (code "42") (name "/Cell-40") (class "Default")
      (node (ref "P4") (pin "16") (pinfunction "16_16") (pintype "passive"))
      (node (ref "R17") (pin "2") (pinfunction "2_2") (pintype "passive"))
    )
    (net (code "43") (name "/Cell-41") (class "Default")
      (node (ref "P4") (pin "17") (pinfunction "17_17") (pintype "passive"))
      (node (ref "R21") (pin "2") (pinfunction "2_2") (pintype "passive"))
    )
    (net (code "44") (name "/Cell-42") (class "Default")
      (node (ref "P4") (pin "18") (pinfunction "18_18") (pintype "passive"))
      (node (ref "R25") (pin "2") (pinfunction "2_2") (pintype "passive"))
    )
    (net (code "45") (name "/Cell-43") (class "Default")
      (node (ref "P4") (pin "19") (pinfunction "19_19") (pintype "passive"))
      (node (ref "R29") (pin "2") (pinfunction "2_2") (pintype "passive"))
    )
    (net (code "46") (name "/Cell-44") (class "Default")
      (node (ref "P4") (pin "20") (pinfunction "20_20") (pintype "passive"))
      (node (ref "R33") (pin "2") (pinfunction "2_2") (pintype "passive"))
    )
    (net (code "47") (name "/Cell-45") (class "Default")
      (node (ref "P3") (pin "1") (pinfunction "1_1") (pintype "passive"))
      (node (ref "R37") (pin "2") (pinfunction "2_2") (pintype "passive"))
    )
    (net (code "48") (name "/Cell-46") (class "Default")
      (node (ref "P3") (pin "2") (pinfunction "2_2") (pintype "passive"))
      (node (ref "R41") (pin "2") (pinfunction "2_2") (pintype "passive"))
    )
    (net (code "49") (name "/Cell-47") (class "Default")
      (node (ref "P3") (pin "3") (pinfunction "3_3") (pintype "passive"))
      (node (ref "R45") (pin "2") (pinfunction "2_2") (pintype "passive"))
    )
    (net (code "50") (name "/Cell-48") (class "Default")
      (node (ref "P3") (pin "4") (pinfunction "4_4") (pintype "passive"))
      (node (ref "R49") (pin "2") (pinfunction "2_2") (pintype "passive"))
    )
    (net (code "51") (name "/CellV") (class "Default")
      (node (ref "R46") (pin "1") (pinfunction "1_1") (pintype "passive"))
    )
    (net (code "52") (name "/CellV_1") (class "Default")
      (node (ref "R12") (pin "1") (pinfunction "1_1") (pintype "passive"))
    )
    (net (code "53") (name "/CellV_2") (class "Default")
      (node (ref "R16") (pin "1") (pinfunction "1_1") (pintype "passive"))
    )
    (net (code "54") (name "/CellV_3") (class "Default")
      (node (ref "R5") (pin "1") (pinfunction "1_1") (pintype "passive"))
    )
    (net (code "55") (name "/CellV_4") (class "Default")
      (node (ref "R9") (pin "1") (pinfunction "1_1") (pintype "passive"))
    )
    (net (code "56") (name "/CellV_5") (class "Default")
      (node (ref "R17") (pin "1") (pinfunction "1_1") (pintype "passive"))
    )
    (net (code "57") (name "/CellV_6") (class "Default")
      (node (ref "R21") (pin "1") (pinfunction "1_1") (pintype "passive"))
    )
    (net (code "58") (name "/CellV_7") (class "Default")
      (node (ref "R25") (pin "1") (pinfunction "1_1") (pintype "passive"))
    )
    (net (code "59") (name "/CellV_8") (class "Default")
      (node (ref "R13") (pin "1") (pinfunction "1_1") (pintype "passive"))
    )
    (net (code "60") (name "/CellV_9") (class "Default")
      (node (ref "R33") (pin "1") (pinfunction "1_1") (pintype "passive"))
    )
    (net (code "61") (name "/CellV_10") (class "Default")
      (node (ref "R29") (pin "1") (pinfunction "1_1") (pintype "passive"))
    )
    (net (code "62") (name "/CellV_11") (class "Default")
      (node (ref "R48") (pin "1") (pinfunction "1_1") (pintype "passive"))
    )
    (net (code "63") (name "/CellV_12") (class "Default")
      (node (ref "R45") (pin "1") (pinfunction "1_1") (pintype "passive"))
    )
    (net (code "64") (name "/CellV_13") (class "Default")
      (node (ref "R37") (pin "1") (pinfunction "1_1") (pintype "passive"))
    )
    (net (code "65") (name "/CellV_14") (class "Default")
      (node (ref "R41") (pin "1") (pinfunction "1_1") (pintype "passive"))
    )
    (net (code "66") (name "/CellV_15") (class "Default")
      (node (ref "R49") (pin "1") (pinfunction "1_1") (pintype "passive"))
    )
    (net (code "67") (name "/CellV_16") (class "Default")
      (node (ref "R6") (pin "1") (pinfunction "1_1") (pintype "passive"))
    )
    (net (code "68") (name "/CellV_17") (class "Default")
      (node (ref "R10") (pin "1") (pinfunction "1_1") (pintype "passive"))
    )
    (net (code "69") (name "/CellV_18") (class "Default")
      (node (ref "R2") (pin "1") (pinfunction "1_1") (pintype "passive"))
    )
    (net (code "70") (name "/CellV_19") (class "Default")
      (node (ref "R3") (pin "1") (pinfunction "1_1") (pintype "passive"))
    )
    (net (code "71") (name "/CellV_20") (class "Default")
      (node (ref "R7") (pin "1") (pinfunction "1_1") (pintype "passive"))
    )
    (net (code "72") (name "/CellV_21") (class "Default")
      (node (ref "R11") (pin "1") (pinfunction "1_1") (pintype "passive"))
    )
    (net (code "73") (name "/CellV_22") (class "Default")
      (node (ref "R14") (pin "1") (pinfunction "1_1") (pintype "passive"))
    )
    (net (code "74") (name "/CellV_23") (class "Default")
      (node (ref "R15") (pin "1") (pinfunction "1_1") (pintype "passive"))
    )
    (net (code "75") (name "/CellV_24") (class "Default")
      (node (ref "R22") (pin "1") (pinfunction "1_1") (pintype "passive"))
    )
    (net (code "76") (name "/CellV_25") (class "Default")
      (node (ref "R18") (pin "1") (pinfunction "1_1") (pintype "passive"))
    )
    (net (code "77") (name "/CellV_26") (class "Default")
      (node (ref "R19") (pin "1") (pinfunction "1_1") (pintype "passive"))
    )
    (net (code "78") (name "/CellV_27") (class "Default")
      (node (ref "R23") (pin "1") (pinfunction "1_1") (pintype "passive"))
    )
    (net (code "79") (name "/CellV_28") (class "Default")
      (node (ref "R4") (pin "1") (pinfunction "1_1") (pintype "passive"))
    )
    (net (code "80") (name "/CellV_29") (class "Default")
      (node (ref "R8") (pin "1") (pinfunction "1_1") (pintype "passive"))
    )
    (net (code "81") (name "/CellV_30") (class "Default")
      (node (ref "R20") (pin "1") (pinfunction "1_1") (pintype "passive"))
    )
    (net (code "82") (name "/CellV_31") (class "Default")
      (node (ref "R32") (pin "1") (pinfunction "1_1") (pintype "passive"))
    )
    (net (code "83") (name "/CellV_32") (class "Default")
      (node (ref "R36") (pin "1") (pinfunction "1_1") (pintype "passive"))
    )
    (net (code "84") (name "/CellV_33") (class "Default")
      (node (ref "R28") (pin "1") (pinfunction "1_1") (pintype "passive"))
    )
    (net (code "85") (name "/CellV_34") (class "Default")
      (node (ref "R24") (pin "1") (pinfunction "1_1") (pintype "passive"))
    )
    (net (code "86") (name "/CellV_35") (class "Default")
      (node (ref "R40") (pin "1") (pinfunction "1_1") (pintype "passive"))
    )
    (net (code "87") (name "/CellV_36") (class "Default")
      (node (ref "R27") (pin "1") (pinfunction "1_1") (pintype "passive"))
    )
    (net (code "88") (name "/CellV_37") (class "Default")
      (node (ref "R31") (pin "1") (pinfunction "1_1") (pintype "passive"))
    )
    (net (code "89") (name "/CellV_38") (class "Default")
      (node (ref "R35") (pin "1") (pinfunction "1_1") (pintype "passive"))
    )
    (net (code "90") (name "/CellV_39") (class "Default")
      (node (ref "R39") (pin "1") (pinfunction "1_1") (pintype "passive"))
    )
    (net (code "91") (name "/CellV_40") (class "Default")
      (node (ref "R43") (pin "1") (pinfunction "1_1") (pintype "passive"))
    )
    (net (code "92") (name "/CellV_41") (class "Default")
      (node (ref "R47") (pin "1") (pinfunction "1_1") (pintype "passive"))
    )
    (net (code "93") (name "/CellV_42") (class "Default")
      (node (ref "R44") (pin "1") (pinfunction "1_1") (pintype "passive"))
    )
    (net (code "94") (name "/CellV_43") (class "Default")
      (node (ref "R26") (pin "1") (pinfunction "1_1") (pintype "passive"))
    )
    (net (code "95") (name "/CellV_44") (class "Default")
      (node (ref "R30") (pin "1") (pinfunction "1_1") (pintype "passive"))
    )
    (net (code "96") (name "/CellV_45") (class "Default")
      (node (ref "R34") (pin "1") (pinfunction "1_1") (pintype "passive"))
    )
    (net (code "97") (name "/CellV_46") (class "Default")
      (node (ref "R38") (pin "1") (pinfunction "1_1") (pintype "passive"))
    )
    (net (code "98") (name "/CellV_47") (class "Default")
      (node (ref "R42") (pin "1") (pinfunction "1_1") (pintype "passive"))
    )
    (net (code "100") (name "/ISO_SCL") (class "Default")
      (node (ref "J5") (pin "1") (pinfunction "1_1") (pintype "passive"))
    )
    (net (code "101") (name "/ISO_SDA") (class "Default")
      (node (ref "J3") (pin "1") (pinfunction "1_1") (pintype "passive"))
    )
    (net (code "102") (name "/NRST") (class "Default")
      (node (ref "C1") (pin "1") (pinfunction "1_1") (pintype "passive"))
      (node (ref "R51") (pin "2") (pinfunction "2_2") (pintype "passive"))
      (node (ref "SW1") (pin "3") (pinfunction "3_3") (pintype "passive"))
      (node (ref "SW1") (pin "4") (pinfunction "4_4") (pintype "passive"))
      (node (ref "U1") (pin "14") (pinfunction "NRST_14") (pintype "bidirectional"))
    )
    (net (code "103") (name "/SCL") (class "Default")
      (node (ref "J2") (pin "1") (pinfunction "1_1") (pintype "passive"))
      (node (ref "U1") (pin "92") (pinfunction "PB6_92") (pintype "bidirectional"))
    )
    (net (code "104") (name "/SCL-MOSI") (class "Default")
      (node (ref "J6") (pin "1") (pinfunction "1_1") (pintype "passive"))
      (node (ref "P1") (pin "5") (pinfunction "5_5") (pintype "passive"))
      (node (ref "P1") (pin "6") (pinfunction "6_6") (pintype "passive"))
      (node (ref "U1") (pin "47") (pinfunction "PB10_47") (pintype "bidirectional"))
    )
    (net (code "105") (name "/SDA") (class "Default")
      (node (ref "J1") (pin "1") (pinfunction "1_1") (pintype "passive"))
      (node (ref "U1") (pin "93") (pinfunction "PB7_93") (pintype "bidirectional"))
    )
    (net (code "106") (name "/SDA-MOSI") (class "Default")
      (node (ref "J4") (pin "1") (pinfunction "1_1") (pintype "passive"))
      (node (ref "P1") (pin "3") (pinfunction "3_3") (pintype "passive"))
      (node (ref "P1") (pin "4") (pinfunction "4_4") (pintype "passive"))
      (node (ref "U1") (pin "48") (pinfunction "PB11_48") (pintype "bidirectional"))
    )
    (net (code "108") (name "/SYS_JTCK-SWCLK") (class "Default")
      (node (ref "U1") (pin "76") (pinfunction "PA14_76") (pintype "bidirectional"))
    )
    (net (code "109") (name "/SYS_JTDI") (class "Default")
      (node (ref "U1") (pin "77") (pinfunction "PA15_77") (pintype "bidirectional"))
    )
    (net (code "110") (name "/SYS_JTDO-TRACESWO") (class "Default")
      (node (ref "U1") (pin "89") (pinfunction "PB3_89") (pintype "bidirectional"))
    )
    (net (code "111") (name "/SYS_JTMS-SWDIO") (class "Default")
      (node (ref "U1") (pin "72") (pinfunction "PA13_72") (pintype "bidirectional"))
    )
    (net (code "112") (name "/SYS_TraceCK") (class "Default")
      (node (ref "U1") (pin "1") (pinfunction "PE2_1") (pintype "bidirectional"))
    )
    (net (code "113") (name "/SYS_TraceD0") (class "Default")
      (node (ref "U1") (pin "2") (pinfunction "PE3_2") (pintype "bidirectional"))
    )
    (net (code "114") (name "/SYS_TraceD1") (class "Default")
      (node (ref "U1") (pin "3") (pinfunction "PE4_3") (pintype "bidirectional"))
    )
    (net (code "115") (name "/SYS_TraceD2") (class "Default")
      (node (ref "U1") (pin "4") (pinfunction "PE5_4") (pintype "bidirectional"))
    )
    (net (code "116") (name "/SYS_TraceD3") (class "Default")
      (node (ref "U1") (pin "5") (pinfunction "PE6-WKUP3_5") (pintype "bidirectional"))
    )
    (net (code "117") (name "/V+") (class "Default")
      (node (ref "J8") (pin "1") (pinfunction "1_1") (pintype "passive"))
      (node (ref "R50") (pin "2") (pinfunction "2_2") (pintype "passive"))
    )
    (net (code "119") (name "/cCell-1") (class "Default")
      (node (ref "U1") (pin "55") (pinfunction "PD8_55") (pintype "bidirectional"))
    )
    (net (code "120") (name "/cCell-2") (class "Default")
      (node (ref "U1") (pin "53") (pinfunction "PB14_53") (pintype "bidirectional"))
    )
    (net (code "121") (name "/cCell-3") (class "Default")
      (node (ref "U1") (pin "51") (pinfunction "PB12_51") (pintype "bidirectional"))
    )
    (net (code "122") (name "/cCell-4") (class "Default")
      (node (ref "U1") (pin "97") (pinfunction "PE0_97") (pintype "bidirectional"))
    )
    (net (code "123") (name "/cCell-5") (class "Default")
      (node (ref "U1") (pin "96") (pinfunction "PB9_96") (pintype "bidirectional"))
    )
    (net (code "124") (name "/cCell-6") (class "Default")
      (node (ref "U1") (pin "95") (pinfunction "PB8_95") (pintype "bidirectional"))
    )
    (net (code "125") (name "/cCell-7") (class "Default")
      (node (ref "U1") (pin "91") (pinfunction "PB5_91") (pintype "bidirectional"))
    )
    (net (code "126") (name "/cCell-8") (class "Default")
      (node (ref "U1") (pin "84") (pinfunction "PD3_84") (pintype "bidirectional"))
    )
    (net (code "127") (name "/cCell-9") (class "Default")
      (node (ref "U1") (pin "85") (pinfunction "PD4_85") (pintype "bidirectional"))
    )
    (net (code "128") (name "/cCell-10") (class "Default")
      (node (ref "U1") (pin "86") (pinfunction "PD5_86") (pintype "bidirectional"))
    )
    (net (code "129") (name "/cCell-11") (class "Default")
      (node (ref "U1") (pin "87") (pinfunction "PD6_87") (pintype "bidirectional"))
    )
    (net (code "130") (name "/cCell-12") (class "Default")
      (node (ref "U1") (pin "88") (pinfunction "PD7_88") (pintype "bidirectional"))
    )
    (net (code "131") (name "/cCell-13") (class "Default")
      (node (ref "U1") (pin "90") (pinfunction "PB4_90") (pintype "bidirectional"))
    )
    (net (code "132") (name "/cCell-14") (class "Default")
      (node (ref "U1") (pin "98") (pinfunction "PE1_98") (pintype "bidirectional"))
    )
    (net (code "133") (name "/cCell-15") (class "Default")
      (node (ref "U1") (pin "32") (pinfunction "PA7_32") (pintype "bidirectional"))
    )
    (net (code "134") (name "/cCell-16") (class "Default")
      (node (ref "U1") (pin "30") (pinfunction "PA5_30") (pintype "bidirectional"))
    )
    (net (code "135") (name "/cCell-17") (class "Default")
      (node (ref "U1") (pin "29") (pinfunction "PA4_29") (pintype "bidirectional"))
    )
    (net (code "136") (name "/cCell-18") (class "Default")
      (node (ref "U1") (pin "52") (pinfunction "PB13_52") (pintype "bidirectional"))
    )
    (net (code "137") (name "/cCell-19") (class "Default")
      (node (ref "U1") (pin "56") (pinfunction "PD9_56") (pintype "bidirectional"))
    )
    (net (code "138") (name "/cCell-20") (class "Default")
      (node (ref "U1") (pin "57") (pinfunction "PD10_57") (pintype "bidirectional"))
    )
    (net (code "139") (name "/cCell-21") (class "Default")
      (node (ref "U1") (pin "31") (pinfunction "PA6_31") (pintype "bidirectional"))
    )
    (net (code "140") (name "/cCell-22") (class "Default")
      (node (ref "U1") (pin "33") (pinfunction "PC4_33") (pintype "bidirectional"))
    )
    (net (code "141") (name "/cCell-23") (class "Default")
      (node (ref "U1") (pin "34") (pinfunction "PC5_34") (pintype "bidirectional"))
    )
    (net (code "142") (name "/cCell-24") (class "Default")
      (node (ref "U1") (pin "54") (pinfunction "PB15_54") (pintype "bidirectional"))
    )
    (net (code "143") (name "/cCell-25") (class "Default")
      (node (ref "U1") (pin "61") (pinfunction "PD14_61") (pintype "bidirectional"))
    )
    (net (code "144") (name "/cCell-26") (class "Default")
      (node (ref "U1") (pin "60") (pinfunction "PD13_60") (pintype "bidirectional"))
    )
    (net (code "145") (name "/cCell-27") (class "Default")
      (node (ref "U1") (pin "59") (pinfunction "PD12_59") (pintype "bidirectional"))
    )
    (net (code "146") (name "/cCell-28") (class "Default")
      (node (ref "U1") (pin "58") (pinfunction "PD11_58") (pintype "bidirectional"))
    )
    (net (code "147") (name "/cCell-29") (class "Default")
      (node (ref "U1") (pin "62") (pinfunction "PD15_62") (pintype "bidirectional"))
    )
    (net (code "148") (name "/cCell-30") (class "Default")
      (node (ref "U1") (pin "67") (pinfunction "PA8_67") (pintype "bidirectional"))
    )
    (net (code "149") (name "/cCell-31") (class "Default")
      (node (ref "U1") (pin "71") (pinfunction "PA12_71") (pintype "bidirectional"))
    )
    (net (code "150") (name "/cCell-32") (class "Default")
      (node (ref "U1") (pin "78") (pinfunction "PC10_78") (pintype "bidirectional"))
    )
    (net (code "151") (name "/cCell-33") (class "Default")
      (node (ref "U1") (pin "79") (pinfunction "PC11_79") (pintype "bidirectional"))
    )
    (net (code "152") (name "/cCell-34") (class "Default")
      (node (ref "U1") (pin "80") (pinfunction "PC12_80") (pintype "bidirectional"))
    )
    (net (code "153") (name "/cCell-35") (class "Default")
      (node (ref "U1") (pin "81") (pinfunction "PD0_81") (pintype "bidirectional"))
    )
    (net (code "154") (name "/cCell-36") (class "Default")
      (node (ref "U1") (pin "82") (pinfunction "PD1_82") (pintype "bidirectional"))
    )
    (net (code "155") (name "/cCell-37") (class "Default")
      (node (ref "U1") (pin "83") (pinfunction "PD2_83") (pintype "bidirectional"))
    )
    (net (code "156") (name "/cCell-38") (class "Default")
      (node (ref "U1") (pin "70") (pinfunction "PA11_70") (pintype "bidirectional"))
    )
    (net (code "157") (name "/cCell-39") (class "Default")
      (node (ref "U1") (pin "69") (pinfunction "PA10_69") (pintype "bidirectional"))
    )
    (net (code "158") (name "/cCell-40") (class "Default")
      (node (ref "U1") (pin "68") (pinfunction "PA9_68") (pintype "bidirectional"))
    )
    (net (code "159") (name "/cCell-41") (class "Default")
      (node (ref "U1") (pin "66") (pinfunction "PC9_66") (pintype "bidirectional"))
    )
    (net (code "160") (name "/cCell-42") (class "Default")
      (node (ref "U1") (pin "65") (pinfunction "PC8_65") (pintype "bidirectional"))
    )
    (net (code "161") (name "/cCell-43") (class "Default")
      (node (ref "U1") (pin "64") (pinfunction "PC7_64") (pintype "bidirectional"))
    )
    (net (code "162") (name "/cCell-44") (class "Default")
      (node (ref "U1") (pin "63") (pinfunction "PC6_63") (pintype "bidirectional"))
    )
    (net (code "163") (name "/cCell-45") (class "Default")
      (node (ref "U1") (pin "43") (pinfunction "PE12_43") (pintype "bidirectional"))
    )
    (net (code "164") (name "/cCell-46") (class "Default")
      (node (ref "U1") (pin "44") (pinfunction "PE13_44") (pintype "bidirectional"))
    )
    (net (code "165") (name "/cCell-47") (class "Default")
      (node (ref "U1") (pin "45") (pinfunction "PE14_45") (pintype "bidirectional"))
    )
    (net (code "166") (name "/cCell-48") (class "Default")
      (node (ref "U1") (pin "46") (pinfunction "PE15_46") (pintype "bidirectional"))
    )
    (net (code "167") (name "3V3") (class "Default")
      (node (ref "C10") (pin "2") (pinfunction "2_2") (pintype "passive"))
      (node (ref "C11") (pin "1") (pinfunction "1_1") (pintype "passive"))
      (node (ref "C12") (pin "2") (pinfunction "2_2") (pintype "passive"))
      (node (ref "C15") (pin "1") (pinfunction "1_1") (pintype "passive"))
      (node (ref "C16") (pin "1") (pinfunction "1_1") (pintype "passive"))
      (node (ref "C3") (pin "1") (pinfunction "1_1") (pintype "passive"))
      (node (ref "C4") (pin "2") (pinfunction "2_2") (pintype "passive"))
      (node (ref "C5") (pin "1") (pinfunction "1_1") (pintype "passive"))
      (node (ref "C6") (pin "2") (pinfunction "2_2") (pintype "passive"))
      (node (ref "C7") (pin "1") (pinfunction "1_1") (pintype "passive"))
      (node (ref "C8") (pin "2") (pinfunction "2_2") (pintype "passive"))
      (node (ref "C9") (pin "1") (pinfunction "1_1") (pintype "passive"))
      (node (ref "J7") (pin "1") (pinfunction "1_1") (pintype "passive"))
      (node (ref "R51") (pin "1") (pinfunction "1_1") (pintype "passive"))
      (node (ref "R52") (pin "1") (pinfunction "1_1") (pintype "passive"))
      (node (ref "U1") (pin "100") (pinfunction "VDD_3_100") (pintype "power_in"))
      (node (ref "U1") (pin "11") (pinfunction "VDD_5_11") (pintype "power_in"))
      (node (ref "U1") (pin "22") (pinfunction "VDDA_22") (pintype "power_in"))
      (node (ref "U1") (pin "28") (pinfunction "VDD_4_28") (pintype "power_in"))
      (node (ref "U1") (pin "50") (pinfunction "VDD_1_50") (pintype "power_in"))
      (node (ref "U1") (pin "75") (pinfunction "VDD_2_75") (pintype "power_in"))
    )
    (net (code "168") (name "5V") (class "Default")
      (node (ref "J10") (pin "1") (pinfunction "1_1") (pintype "passive"))
      (node (ref "P1") (pin "7") (pinfunction "7_7") (pintype "passive"))
      (node (ref "P1") (pin "8") (pinfunction "8_8") (pintype "passive"))
    )
    (net (code "169") (name "GND") (class "Default")
      (node (ref "C1") (pin "2") (pinfunction "2_2") (pintype "passive"))
      (node (ref "C10") (pin "1") (pinfunction "1_1") (pintype "passive"))
      (node (ref "C11") (pin "2") (pinfunction "2_2") (pintype "passive"))
      (node (ref "C12") (pin "1") (pinfunction "1_1") (pintype "passive"))
      (node (ref "C13") (pin "2") (pinfunction "2_2") (pintype "passive"))
      (node (ref "C14") (pin "2") (pinfunction "2_2") (pintype "passive"))
      (node (ref "C15") (pin "2") (pinfunction "2_2") (pintype "passive"))
      (node (ref "C16") (pin "2") (pinfunction "2_2") (pintype "passive"))
      (node (ref "C2") (pin "2") (pinfunction "2_2") (pintype "passive"))
      (node (ref "C3") (pin "2") (pinfunction "2_2") (pintype "passive"))
      (node (ref "C4") (pin "1") (pinfunction "1_1") (pintype "passive"))
      (node (ref "C5") (pin "2") (pinfunction "2_2") (pintype "passive"))
      (node (ref "C6") (pin "1") (pinfunction "1_1") (pintype "passive"))
      (node (ref "C7") (pin "2") (pinfunction "2_2") (pintype "passive"))
      (node (ref "C8") (pin "1") (pinfunction "1_1") (pintype "passive"))
      (node (ref "C9") (pin "2") (pinfunction "2_2") (pintype "passive"))
      (node (ref "J12") (pin "1") (pinfunction "1_1") (pintype "passive"))
      (node (ref "P1") (pin "1") (pinfunction "1_1") (pintype "passive"))
      (node (ref "P1") (pin "2") (pinfunction "2_2") (pintype "passive"))
      (node (ref "SW1") (pin "1") (pinfunction "1_1") (pintype "passive"))
      (node (ref "SW1") (pin "2") (pinfunction "2_2") (pintype "passive"))
      (node (ref "SW2") (pin "1") (pinfunction "1_1") (pintype "passive"))
      (node (ref "SW2") (pin "2") (pinfunction "2_2") (pintype "passive"))
      (node (ref "U1") (pin "10") (pinfunction "VSS_5_10") (pintype "power_in"))
      (node (ref "U1") (pin "19") (pinfunction "VSSA_19") (pintype "power_in"))
      (node (ref "U1") (pin "20") (pinfunction "VREF-_20") (pintype "power_in"))
      (node (ref "U1") (pin "27") (pinfunction "VSS_4_27") (pintype "power_in"))
      (node (ref "U1") (pin "49") (pinfunction "VSS_1_49") (pintype "power_in"))
      (node (ref "U1") (pin "74") (pinfunction "VSS_2_74") (pintype "power_in"))
      (node (ref "U1") (pin "99") (pinfunction "VSS_3_99") (pintype "power_in"))
    )
    (net (code "170") (name "ISO_5V") (class "Default")
      (node (ref "J11") (pin "1") (pinfunction "1_1") (pintype "passive"))
    )
    (net (code "171") (name "ISO_GND") (class "Default")
      (node (ref "J13") (pin "1") (pinfunction "1_1") (pintype "passive"))
      (node (ref "R50") (pin "1") (pinfunction "1_1") (pintype "passive"))
    )
    (net (code "172") (name "Vref") (class "Default")
      (node (ref "C13") (pin "1") (pinfunction "1_1") (pintype "passive"))
      (node (ref "C14") (pin "1") (pinfunction "1_1") (pintype "passive"))
      (node (ref "J9") (pin "1") (pinfunction "1_1") (pintype "passive"))
      (node (ref "U1") (pin "21") (pinfunction "VREF+_21") (pintype "power_in"))
    )
    (net (code "173") (name "unconnected-(U1A-PA0-WKUP1-Pad23)") (class "Default")
      (node (ref "U1") (pin "23") (pinfunction "PA0-WKUP1_23") (pintype "bidirectional"))
    )
    (net (code "174") (name "unconnected-(U1A-PA1-Pad24)") (class "Default")
      (node (ref "U1") (pin "24") (pinfunction "PA1_24") (pintype "bidirectional"))
    )
    (net (code "175") (name "unconnected-(U1A-PA2-Pad25)") (class "Default")
      (node (ref "U1") (pin "25") (pinfunction "PA2_25") (pintype "bidirectional"))
    )
    (net (code "176") (name "unconnected-(U1A-PA3-Pad26)") (class "Default")
      (node (ref "U1") (pin "26") (pinfunction "PA3_26") (pintype "bidirectional"))
    )
    (net (code "177") (name "unconnected-(U1A-PB0-Pad35)") (class "Default")
      (node (ref "U1") (pin "35") (pinfunction "PB0_35") (pintype "bidirectional"))
    )
    (net (code "178") (name "unconnected-(U1A-PB1-Pad36)") (class "Default")
      (node (ref "U1") (pin "36") (pinfunction "PB1_36") (pintype "bidirectional"))
    )
    (net (code "179") (name "unconnected-(U1A-PB2-Pad37)") (class "Default")
      (node (ref "U1") (pin "37") (pinfunction "PB2_37") (pintype "bidirectional"))
    )
    (net (code "180") (name "unconnected-(U1A-PC0-Pad15)") (class "Default")
      (node (ref "U1") (pin "15") (pinfunction "PC0_15") (pintype "bidirectional"))
    )
    (net (code "181") (name "unconnected-(U1A-PC1-Pad16)") (class "Default")
      (node (ref "U1") (pin "16") (pinfunction "PC1_16") (pintype "bidirectional"))
    )
    (net (code "182") (name "unconnected-(U1A-PC2-Pad17)") (class "Default")
      (node (ref "U1") (pin "17") (pinfunction "PC2_17") (pintype "bidirectional"))
    )
    (net (code "183") (name "unconnected-(U1A-PC3-Pad18)") (class "Default")
      (node (ref "U1") (pin "18") (pinfunction "PC3_18") (pintype "bidirectional"))
    )
    (net (code "184") (name "unconnected-(U1A-PC13-WKUP2-Pad7)") (class "Default")
      (node (ref "U1") (pin "7") (pinfunction "PC13-WKUP2_7") (pintype "bidirectional"))
    )
    (net (code "185") (name "unconnected-(U1A-PC14-OSC32_IN-Pad8)") (class "Default")
      (node (ref "U1") (pin "8") (pinfunction "PC14-OSC32_IN_8") (pintype "bidirectional"))
    )
    (net (code "186") (name "unconnected-(U1A-PC15-OSC32_OUT-Pad9)") (class "Default")
      (node (ref "U1") (pin "9") (pinfunction "PC15-OSC32_OUT_9") (pintype "bidirectional"))
    )
    (net (code "187") (name "unconnected-(U1A-PE7-Pad38)") (class "Default")
      (node (ref "U1") (pin "38") (pinfunction "PE7_38") (pintype "bidirectional"))
    )
    (net (code "188") (name "unconnected-(U1A-PE8-Pad39)") (class "Default")
      (node (ref "U1") (pin "39") (pinfunction "PE8_39") (pintype "bidirectional"))
    )
    (net (code "189") (name "unconnected-(U1A-PE9-Pad40)") (class "Default")
      (node (ref "U1") (pin "40") (pinfunction "PE9_40") (pintype "bidirectional"))
    )
    (net (code "190") (name "unconnected-(U1A-PE10-Pad41)") (class "Default")
      (node (ref "U1") (pin "41") (pinfunction "PE10_41") (pintype "bidirectional"))
    )
    (net (code "191") (name "unconnected-(U1A-PE11-Pad42)") (class "Default")
      (node (ref "U1") (pin "42") (pinfunction "PE11_42") (pintype "bidirectional"))
    )
    (net (code "192") (name "unconnected-(U1A-PH0-OSC_IN-Pad12)") (class "Default")
      (node (ref "U1") (pin "12") (pinfunction "PH0-OSC_IN_12") (pintype "bidirectional"))
    )
    (net (code "193") (name "unconnected-(U1A-PH1-OSC_OUT-Pad13)") (class "Default")
      (node (ref "U1") (pin "13") (pinfunction "PH1-OSC_OUT_13") (pintype "bidirectional"))
    )
    (net (code "194") (name "unconnected-(U1A-PH2-Pad73)") (class "Default")
      (node (ref "U1") (pin "73") (pinfunction "PH2_73") (pintype "bidirectional"))
    )
    (net (code "195") (name "unconnected-(U1B-VLCD-Pad6)") (class "Default")
      (node (ref "U1") (pin "6") (pinfunction "VLCD_6") (pintype "power_in"))
    )
  )
)
